# proyecto.net
KiCad netlist of a schematic drawn in EAGLE
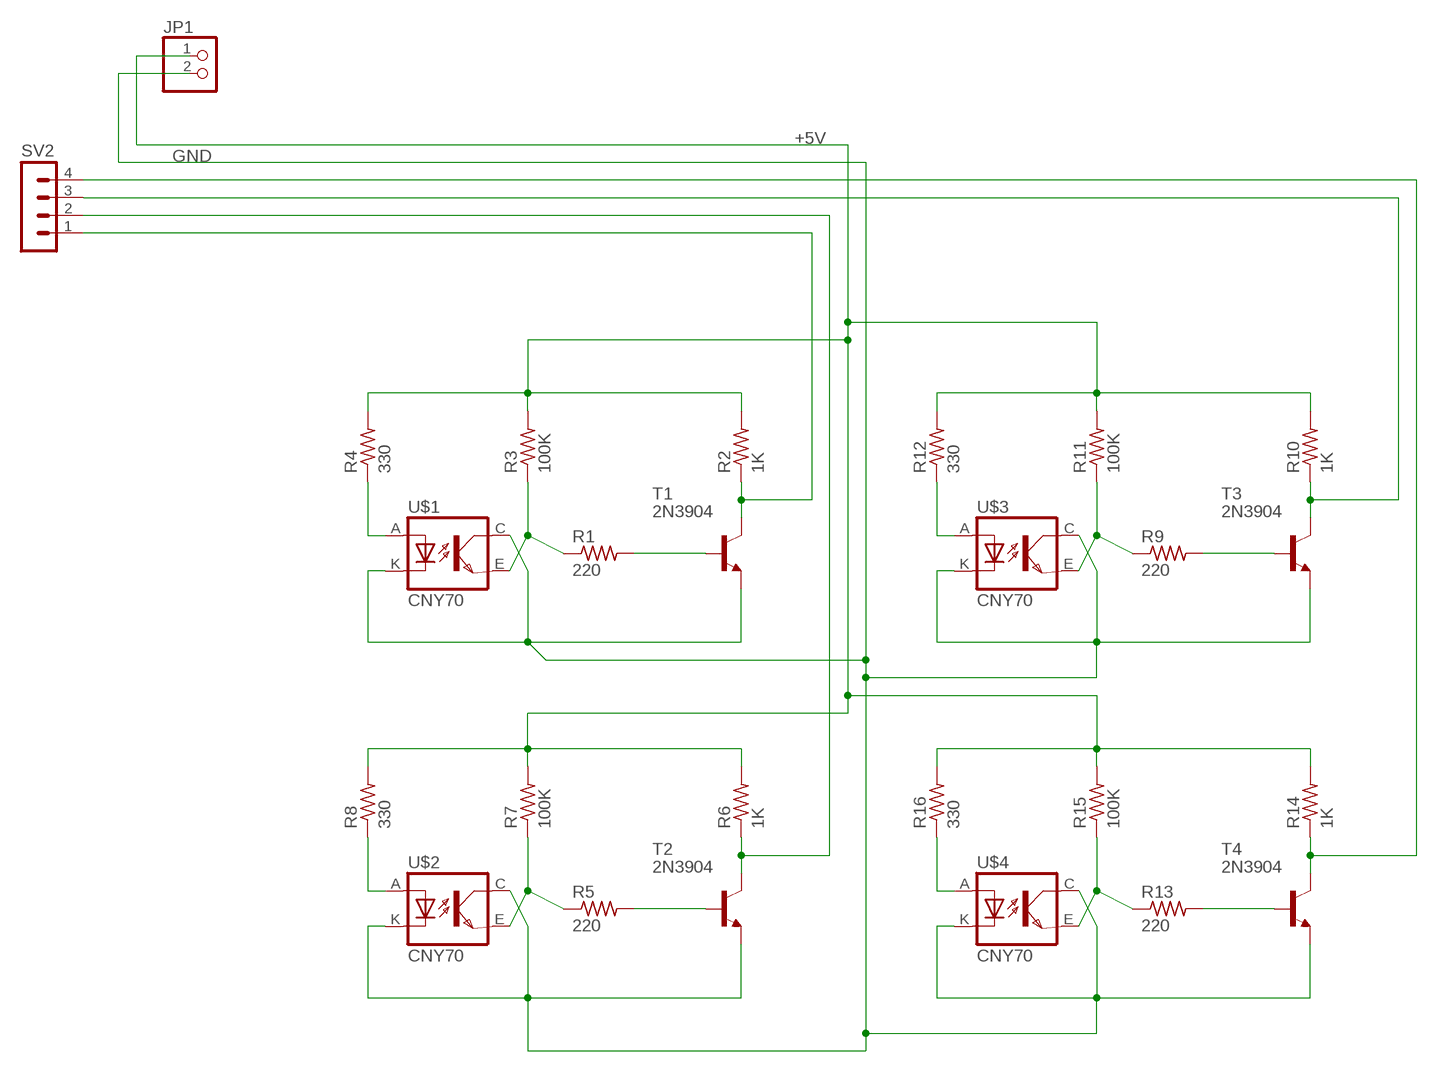
[diagram p0: schematic, sheet 1]

(export (version "E")
  (design (tool "Eeschema 10.0.6"))
  (components
    (comp (ref "JP1")
      (value "PINHD-1X2")
      (footprint "eagle-import:1X02")
      (libsource (lib "eagle-import") (part "PINHD-1X2"))
    )
    (comp (ref "R1")
      (value "220")
      (footprint "eagle-import:0207_10")
      (libsource (lib "eagle-import") (part "R-US_0207/10"))
    )
    (comp (ref "R2")
      (value "1K")
      (footprint "eagle-import:0207_10")
      (libsource (lib "eagle-import") (part "R-US_0207/10"))
    )
    (comp (ref "R3")
      (value "100K")
      (footprint "eagle-import:0207_10")
      (libsource (lib "eagle-import") (part "R-US_0207/10"))
    )
    (comp (ref "R4")
      (value "330")
      (footprint "eagle-import:0207_10")
      (libsource (lib "eagle-import") (part "R-US_0207/10"))
    )
    (comp (ref "R5")
      (value "220")
      (footprint "eagle-import:0207_10")
      (libsource (lib "eagle-import") (part "R-US_0207/10"))
    )
    (comp (ref "R6")
      (value "1K")
      (footprint "eagle-import:0207_10")
      (libsource (lib "eagle-import") (part "R-US_0207/10"))
    )
    (comp (ref "R7")
      (value "100K")
      (footprint "eagle-import:0207_10")
      (libsource (lib "eagle-import") (part "R-US_0207/10"))
    )
    (comp (ref "R8")
      (value "330")
      (footprint "eagle-import:0207_10")
      (libsource (lib "eagle-import") (part "R-US_0207/10"))
    )
    (comp (ref "R9")
      (value "220")
      (footprint "eagle-import:0207_10")
      (libsource (lib "eagle-import") (part "R-US_0207/10"))
    )
    (comp (ref "R10")
      (value "1K")
      (footprint "eagle-import:0207_10")
      (libsource (lib "eagle-import") (part "R-US_0207/10"))
    )
    (comp (ref "R11")
      (value "100K")
      (footprint "eagle-import:0207_10")
      (libsource (lib "eagle-import") (part "R-US_0207/10"))
    )
    (comp (ref "R12")
      (value "330")
      (footprint "eagle-import:0207_10")
      (libsource (lib "eagle-import") (part "R-US_0207/10"))
    )
    (comp (ref "R13")
      (value "220")
      (footprint "eagle-import:0207_10")
      (libsource (lib "eagle-import") (part "R-US_0207/10"))
    )
    (comp (ref "R14")
      (value "1K")
      (footprint "eagle-import:0207_10")
      (libsource (lib "eagle-import") (part "R-US_0207/10"))
    )
    (comp (ref "R15")
      (value "100K")
      (footprint "eagle-import:0207_10")
      (libsource (lib "eagle-import") (part "R-US_0207/10"))
    )
    (comp (ref "R16")
      (value "330")
      (footprint "eagle-import:0207_10")
      (libsource (lib "eagle-import") (part "R-US_0207/10"))
    )
    (comp (ref "SV2")
      (value "MA04-1")
      (footprint "eagle-import:MA04-1")
      (libsource (lib "eagle-import") (part "MA04-1"))
    )
    (comp (ref "T1")
      (value "2N3904")
      (footprint "eagle-import:TO92")
      (libsource (lib "eagle-import") (part "2N3904"))
    )
    (comp (ref "T2")
      (value "2N3904")
      (footprint "eagle-import:TO92")
      (libsource (lib "eagle-import") (part "2N3904"))
    )
    (comp (ref "T3")
      (value "2N3904")
      (footprint "eagle-import:TO92")
      (libsource (lib "eagle-import") (part "2N3904"))
    )
    (comp (ref "T4")
      (value "2N3904")
      (footprint "eagle-import:TO92")
      (libsource (lib "eagle-import") (part "2N3904"))
    )
    (comp (ref "U$1")
      (value "CNY70")
      (footprint "eagle-import:4")
      (libsource (lib "eagle-import") (part "CNY70"))
    )
    (comp (ref "U$2")
      (value "CNY70")
      (footprint "eagle-import:4")
      (libsource (lib "eagle-import") (part "CNY70"))
    )
    (comp (ref "U$3")
      (value "CNY70")
      (footprint "eagle-import:4")
      (libsource (lib "eagle-import") (part "CNY70"))
    )
    (comp (ref "U$4")
      (value "CNY70")
      (footprint "eagle-import:4")
      (libsource (lib "eagle-import") (part "CNY70"))
    )
  )
  (nets
    (net (code "1") (name "/+5V") (class "Default")
      (node (ref "JP1") (pin "1") (pinfunction "1_1") (pintype "passive"))
      (node (ref "R10") (pin "2") (pinfunction "2_2") (pintype "passive"))
      (node (ref "R11") (pin "2") (pinfunction "2_2") (pintype "passive"))
      (node (ref "R12") (pin "2") (pinfunction "2_2") (pintype "passive"))
      (node (ref "R14") (pin "2") (pinfunction "2_2") (pintype "passive"))
      (node (ref "R15") (pin "2") (pinfunction "2_2") (pintype "passive"))
      (node (ref "R16") (pin "2") (pinfunction "2_2") (pintype "passive"))
      (node (ref "R2") (pin "2") (pinfunction "2_2") (pintype "passive"))
      (node (ref "R3") (pin "2") (pinfunction "2_2") (pintype "passive"))
      (node (ref "R4") (pin "2") (pinfunction "2_2") (pintype "passive"))
      (node (ref "R6") (pin "2") (pinfunction "2_2") (pintype "passive"))
      (node (ref "R7") (pin "2") (pinfunction "2_2") (pintype "passive"))
      (node (ref "R8") (pin "2") (pinfunction "2_2") (pintype "passive"))
    )
    (net (code "2") (name "/GND") (class "Default")
      (node (ref "JP1") (pin "2") (pinfunction "2_2") (pintype "passive"))
      (node (ref "T1") (pin "3") (pinfunction "E_3") (pintype "passive"))
      (node (ref "T2") (pin "3") (pinfunction "E_3") (pintype "passive"))
      (node (ref "T3") (pin "3") (pinfunction "E_3") (pintype "passive"))
      (node (ref "T4") (pin "3") (pinfunction "E_3") (pintype "passive"))
      (node (ref "U$1") (pin "C") (pinfunction "COL_C") (pintype "passive"))
      (node (ref "U$1") (pin "K") (pinfunction "C_K") (pintype "passive"))
      (node (ref "U$2") (pin "C") (pinfunction "COL_C") (pintype "passive"))
      (node (ref "U$2") (pin "K") (pinfunction "C_K") (pintype "passive"))
      (node (ref "U$3") (pin "C") (pinfunction "COL_C") (pintype "passive"))
      (node (ref "U$3") (pin "K") (pinfunction "C_K") (pintype "passive"))
      (node (ref "U$4") (pin "C") (pinfunction "COL_C") (pintype "passive"))
      (node (ref "U$4") (pin "K") (pinfunction "C_K") (pintype "passive"))
    )
    (net (code "3") (name "Net-(R4-Pad1)") (class "Default")
      (node (ref "R4") (pin "1") (pinfunction "1_1") (pintype "passive"))
      (node (ref "U$1") (pin "A") (pinfunction "A_A") (pintype "passive"))
    )
    (net (code "4") (name "Net-(R8-Pad1)") (class "Default")
      (node (ref "R8") (pin "1") (pinfunction "1_1") (pintype "passive"))
      (node (ref "U$2") (pin "A") (pinfunction "A_A") (pintype "passive"))
    )
    (net (code "5") (name "Net-(R12-Pad1)") (class "Default")
      (node (ref "R12") (pin "1") (pinfunction "1_1") (pintype "passive"))
      (node (ref "U$3") (pin "A") (pinfunction "A_A") (pintype "passive"))
    )
    (net (code "6") (name "Net-(R16-Pad1)") (class "Default")
      (node (ref "R16") (pin "1") (pinfunction "1_1") (pintype "passive"))
      (node (ref "U$4") (pin "A") (pinfunction "A_A") (pintype "passive"))
    )
    (net (code "7") (name "Net-(T1-B)") (class "Default")
      (node (ref "R1") (pin "2") (pinfunction "2_2") (pintype "passive"))
      (node (ref "T1") (pin "2") (pinfunction "B_2") (pintype "passive"))
    )
    (net (code "8") (name "Net-(T1-C)") (class "Default")
      (node (ref "R2") (pin "1") (pinfunction "1_1") (pintype "passive"))
      (node (ref "SV2") (pin "1") (pinfunction "1_1") (pintype "passive"))
      (node (ref "T1") (pin "1") (pinfunction "C_1") (pintype "passive"))
    )
    (net (code "9") (name "Net-(T2-B)") (class "Default")
      (node (ref "R5") (pin "2") (pinfunction "2_2") (pintype "passive"))
      (node (ref "T2") (pin "2") (pinfunction "B_2") (pintype "passive"))
    )
    (net (code "10") (name "Net-(T2-C)") (class "Default")
      (node (ref "R6") (pin "1") (pinfunction "1_1") (pintype "passive"))
      (node (ref "SV2") (pin "2") (pinfunction "2_2") (pintype "passive"))
      (node (ref "T2") (pin "1") (pinfunction "C_1") (pintype "passive"))
    )
    (net (code "11") (name "Net-(T3-B)") (class "Default")
      (node (ref "R9") (pin "2") (pinfunction "2_2") (pintype "passive"))
      (node (ref "T3") (pin "2") (pinfunction "B_2") (pintype "passive"))
    )
    (net (code "12") (name "Net-(T3-C)") (class "Default")
      (node (ref "R10") (pin "1") (pinfunction "1_1") (pintype "passive"))
      (node (ref "SV2") (pin "3") (pinfunction "3_3") (pintype "passive"))
      (node (ref "T3") (pin "1") (pinfunction "C_1") (pintype "passive"))
    )
    (net (code "13") (name "Net-(T4-B)") (class "Default")
      (node (ref "R13") (pin "2") (pinfunction "2_2") (pintype "passive"))
      (node (ref "T4") (pin "2") (pinfunction "B_2") (pintype "passive"))
    )
    (net (code "14") (name "Net-(T4-C)") (class "Default")
      (node (ref "R14") (pin "1") (pinfunction "1_1") (pintype "passive"))
      (node (ref "SV2") (pin "4") (pinfunction "4_4") (pintype "passive"))
      (node (ref "T4") (pin "1") (pinfunction "C_1") (pintype "passive"))
    )
    (net (code "15") (name "Net-(U$1-EMI)") (class "Default")
      (node (ref "R1") (pin "1") (pinfunction "1_1") (pintype "passive"))
      (node (ref "R3") (pin "1") (pinfunction "1_1") (pintype "passive"))
      (node (ref "U$1") (pin "E") (pinfunction "EMI_E") (pintype "passive"))
    )
    (net (code "16") (name "Net-(U$2-EMI)") (class "Default")
      (node (ref "R5") (pin "1") (pinfunction "1_1") (pintype "passive"))
      (node (ref "R7") (pin "1") (pinfunction "1_1") (pintype "passive"))
      (node (ref "U$2") (pin "E") (pinfunction "EMI_E") (pintype "passive"))
    )
    (net (code "17") (name "Net-(U$3-EMI)") (class "Default")
      (node (ref "R11") (pin "1") (pinfunction "1_1") (pintype "passive"))
      (node (ref "R9") (pin "1") (pinfunction "1_1") (pintype "passive"))
      (node (ref "U$3") (pin "E") (pinfunction "EMI_E") (pintype "passive"))
    )
    (net (code "18") (name "Net-(U$4-EMI)") (class "Default")
      (node (ref "R13") (pin "1") (pinfunction "1_1") (pintype "passive"))
      (node (ref "R15") (pin "1") (pinfunction "1_1") (pintype "passive"))
      (node (ref "U$4") (pin "E") (pinfunction "EMI_E") (pintype "passive"))
    )
  )
)
